# TRAY5.net
KiCad netlist of a schematic drawn in Altium Designer
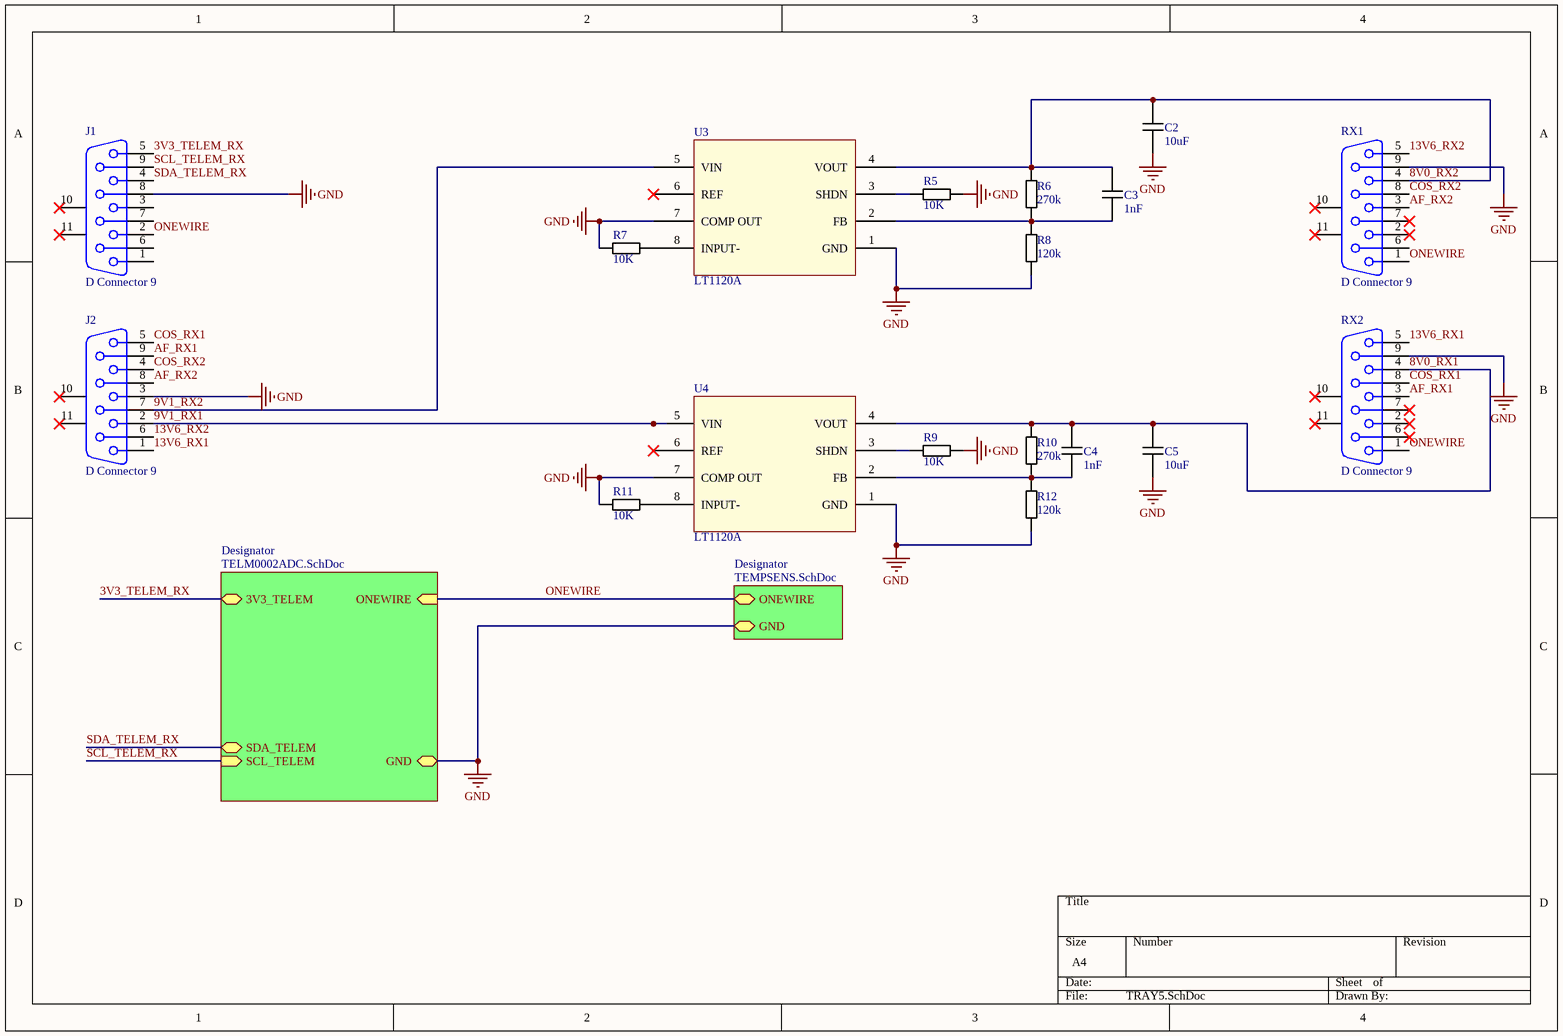
[diagram p0: TRAY5.SchDoc]

(export (version "E")
  (design (tool "Eeschema 10.0.6"))
  (components
    (comp (ref "C2")
      (value "10uF")
      (footprint "0805 Cap")
      (description "0805 MLCC - NP0, 5%")
      (fields (field (name "Comment") "0805 Cap"))
      (libsource (lib "Schlib1") (part "0805 MLCC - NP0, 5%"))
    )
    (comp (ref "C3")
      (value "1nF")
      (footprint "0805 Cap")
      (description "0805 MLCC - NP0, 5%")
      (fields (field (name "Comment") "0805 Cap"))
      (libsource (lib "Schlib1") (part "0805 MLCC - NP0, 5%"))
    )
    (comp (ref "C4")
      (value "1nF")
      (footprint "0805 Cap")
      (description "0805 MLCC - NP0, 5%")
      (fields (field (name "Comment") "0805 Cap"))
      (libsource (lib "Schlib1") (part "0805 MLCC - NP0, 5%"))
    )
    (comp (ref "C5")
      (value "10uF")
      (footprint "0805 Cap")
      (description "0805 MLCC - NP0, 5%")
      (fields (field (name "Comment") "0805 Cap"))
      (libsource (lib "Schlib1") (part "0805 MLCC - NP0, 5%"))
    )
    (comp (ref "J1")
      (value "D Connector 9")
      (footprint "DSUB1.385-2H9")
      (description "Receptacle Assembly, 9 Position, Right Angle")
      (libsource (lib "Miscellaneous Connectors") (part "D Connector 9"))
    )
    (comp (ref "J2")
      (value "D Connector 9")
      (footprint "DSUB1.385-2H9")
      (description "Receptacle Assembly, 9 Position, Right Angle")
      (libsource (lib "Miscellaneous Connectors") (part "D Connector 9"))
    )
    (comp (ref "R5")
      (value "10K")
      (footprint "0805 Resistor")
      (description "0805 Thick Film Resistor 1%")
      (fields (field (name "Comment") "0805 Resistor"))
      (libsource (lib "") (part "0805 Thick Film Resistor 1%_1"))
    )
    (comp (ref "R6")
      (value "270k")
      (footprint "0805 Resistor")
      (description "0805 Thick Film Resistor 1%")
      (fields (field (name "Comment") "0805 Resistor"))
      (libsource (lib "Schlib1") (part "0805 Thick Film Resistor 1%"))
    )
    (comp (ref "R7")
      (value "10K")
      (footprint "0805 Resistor")
      (description "0805 Thick Film Resistor 1%")
      (fields (field (name "Comment") "0805 Resistor"))
      (libsource (lib "") (part "0805 Thick Film Resistor 1%_1"))
    )
    (comp (ref "R8")
      (value "120k")
      (footprint "0805 Resistor")
      (description "0805 Thick Film Resistor 1%")
      (fields (field (name "Comment") "0805 Resistor"))
      (libsource (lib "Schlib1") (part "0805 Thick Film Resistor 1%"))
    )
    (comp (ref "R9")
      (value "10K")
      (footprint "0805 Resistor")
      (description "0805 Thick Film Resistor 1%")
      (fields (field (name "Comment") "0805 Resistor"))
      (libsource (lib "") (part "0805 Thick Film Resistor 1%_1"))
    )
    (comp (ref "R10")
      (value "270k")
      (footprint "0805 Resistor")
      (description "0805 Thick Film Resistor 1%")
      (fields (field (name "Comment") "0805 Resistor"))
      (libsource (lib "Schlib1") (part "0805 Thick Film Resistor 1%"))
    )
    (comp (ref "R11")
      (value "10K")
      (footprint "0805 Resistor")
      (description "0805 Thick Film Resistor 1%")
      (fields (field (name "Comment") "0805 Resistor"))
      (libsource (lib "") (part "0805 Thick Film Resistor 1%_1"))
    )
    (comp (ref "R12")
      (value "120k")
      (footprint "0805 Resistor")
      (description "0805 Thick Film Resistor 1%")
      (fields (field (name "Comment") "0805 Resistor"))
      (libsource (lib "Schlib1") (part "0805 Thick Film Resistor 1%"))
    )
    (comp (ref "RX1")
      (value "D Connector 9")
      (footprint "DSUB Upright")
      (description "Receptacle Assembly, 9 Position, Right Angle")
      (libsource (lib "Miscellaneous Connectors") (part "D Connector 9"))
    )
    (comp (ref "RX2")
      (value "D Connector 9")
      (footprint "DSUB Upright")
      (description "Receptacle Assembly, 9 Position, Right Angle")
      (libsource (lib "Miscellaneous Connectors") (part "D Connector 9"))
    )
    (comp (ref "U3")
      (value "LT1120A")
      (footprint "SOIC8 - LT1120A")
      (libsource (lib "Schlib1") (part "LT1120A"))
    )
    (comp (ref "U4")
      (value "LT1120A")
      (footprint "SOIC8 - LT1120A")
      (libsource (lib "Schlib1") (part "LT1120A"))
    )
  )
  (nets
    (net (code "1") (name "/3V3_TELEM_RX") (class "Default")
      (node (ref "J1") (pin "5") (pinfunction "5_5") (pintype "passive"))
    )
    (net (code "2") (name "/8V0_RX1") (class "Default")
      (node (ref "C4") (pin "2") (pinfunction "2_2") (pintype "passive"))
      (node (ref "C5") (pin "2") (pinfunction "2_2") (pintype "passive"))
      (node (ref "R10") (pin "2") (pinfunction "2_2") (pintype "passive"))
      (node (ref "RX2") (pin "4") (pinfunction "4_4") (pintype "passive"))
      (node (ref "U4") (pin "4") (pinfunction "VOUT_4") (pintype "passive"))
    )
    (net (code "3") (name "/8V0_RX2") (class "Default")
      (node (ref "C2") (pin "2") (pinfunction "2_2") (pintype "passive"))
      (node (ref "C3") (pin "2") (pinfunction "2_2") (pintype "passive"))
      (node (ref "R6") (pin "2") (pinfunction "2_2") (pintype "passive"))
      (node (ref "RX1") (pin "4") (pinfunction "4_4") (pintype "passive"))
      (node (ref "U3") (pin "4") (pinfunction "VOUT_4") (pintype "passive"))
    )
    (net (code "4") (name "/9V1_RX1") (class "Default")
      (node (ref "J2") (pin "2") (pinfunction "2_2") (pintype "passive"))
      (node (ref "U4") (pin "5") (pinfunction "VIN_5") (pintype "passive"))
    )
    (net (code "5") (name "/9V1_RX2") (class "Default")
      (node (ref "J2") (pin "7") (pinfunction "7_7") (pintype "passive"))
      (node (ref "U3") (pin "5") (pinfunction "VIN_5") (pintype "passive"))
    )
    (net (code "6") (name "/13V6_RX1") (class "Default")
      (node (ref "J2") (pin "1") (pinfunction "1_1") (pintype "passive"))
      (node (ref "RX2") (pin "5") (pinfunction "5_5") (pintype "passive"))
    )
    (net (code "7") (name "/13V6_RX2") (class "Default")
      (node (ref "J2") (pin "6") (pinfunction "6_6") (pintype "passive"))
      (node (ref "RX1") (pin "5") (pinfunction "5_5") (pintype "passive"))
    )
    (net (code "8") (name "/AF_RX1") (class "Default")
      (node (ref "J2") (pin "9") (pinfunction "9_9") (pintype "passive"))
      (node (ref "RX2") (pin "3") (pinfunction "3_3") (pintype "passive"))
    )
    (net (code "9") (name "/AF_RX2") (class "Default")
      (node (ref "J2") (pin "8") (pinfunction "8_8") (pintype "passive"))
      (node (ref "RX1") (pin "3") (pinfunction "3_3") (pintype "passive"))
    )
    (net (code "10") (name "/COS_RX1") (class "Default")
      (node (ref "J2") (pin "5") (pinfunction "5_5") (pintype "passive"))
      (node (ref "RX2") (pin "8") (pinfunction "8_8") (pintype "passive"))
    )
    (net (code "11") (name "/COS_RX2") (class "Default")
      (node (ref "J2") (pin "4") (pinfunction "4_4") (pintype "passive"))
      (node (ref "RX1") (pin "8") (pinfunction "8_8") (pintype "passive"))
    )
    (net (code "12") (name "/ONEWIRE") (class "Default")
      (node (ref "J1") (pin "2") (pinfunction "2_2") (pintype "passive"))
      (node (ref "RX1") (pin "1") (pinfunction "1_1") (pintype "passive"))
      (node (ref "RX2") (pin "1") (pinfunction "1_1") (pintype "passive"))
    )
    (net (code "13") (name "/SCL_TELEM_RX") (class "Default")
      (node (ref "J1") (pin "9") (pinfunction "9_9") (pintype "passive"))
    )
    (net (code "14") (name "/SDA_TELEM_RX") (class "Default")
      (node (ref "J1") (pin "4") (pinfunction "4_4") (pintype "passive"))
    )
    (net (code "15") (name "GND") (class "Default")
      (node (ref "C2") (pin "1") (pinfunction "1_1") (pintype "passive"))
      (node (ref "C5") (pin "1") (pinfunction "1_1") (pintype "passive"))
      (node (ref "J1") (pin "8") (pinfunction "8_8") (pintype "passive"))
      (node (ref "J2") (pin "3") (pinfunction "3_3") (pintype "passive"))
      (node (ref "R11") (pin "1") (pinfunction "1_1") (pintype "passive"))
      (node (ref "R12") (pin "1") (pinfunction "1_1") (pintype "passive"))
      (node (ref "R5") (pin "2") (pinfunction "2_2") (pintype "passive"))
      (node (ref "R7") (pin "1") (pinfunction "1_1") (pintype "passive"))
      (node (ref "R8") (pin "1") (pinfunction "1_1") (pintype "passive"))
      (node (ref "R9") (pin "2") (pinfunction "2_2") (pintype "passive"))
      (node (ref "RX1") (pin "9") (pinfunction "9_9") (pintype "passive"))
      (node (ref "RX2") (pin "9") (pinfunction "9_9") (pintype "passive"))
      (node (ref "U3") (pin "1") (pinfunction "GND_1") (pintype "passive"))
      (node (ref "U3") (pin "7") (pinfunction "COMP_OUT_7") (pintype "passive"))
      (node (ref "U4") (pin "1") (pinfunction "GND_1") (pintype "passive"))
      (node (ref "U4") (pin "7") (pinfunction "COMP_OUT_7") (pintype "passive"))
    )
    (net (code "16") (name "Net-(U3-FB)") (class "Default")
      (node (ref "C3") (pin "1") (pinfunction "1_1") (pintype "passive"))
      (node (ref "R6") (pin "1") (pinfunction "1_1") (pintype "passive"))
      (node (ref "R8") (pin "2") (pinfunction "2_2") (pintype "passive"))
      (node (ref "U3") (pin "2") (pinfunction "FB_2") (pintype "passive"))
    )
    (net (code "17") (name "Net-(U3-INPUT-)") (class "Default")
      (node (ref "R7") (pin "2") (pinfunction "2_2") (pintype "passive"))
      (node (ref "U3") (pin "8") (pinfunction "INPUT-_8") (pintype "passive"))
    )
    (net (code "18") (name "Net-(U3-SHDN)") (class "Default")
      (node (ref "R5") (pin "1") (pinfunction "1_1") (pintype "passive"))
      (node (ref "U3") (pin "3") (pinfunction "SHDN_3") (pintype "passive"))
    )
    (net (code "19") (name "Net-(U4-FB)") (class "Default")
      (node (ref "C4") (pin "1") (pinfunction "1_1") (pintype "passive"))
      (node (ref "R10") (pin "1") (pinfunction "1_1") (pintype "passive"))
      (node (ref "R12") (pin "2") (pinfunction "2_2") (pintype "passive"))
      (node (ref "U4") (pin "2") (pinfunction "FB_2") (pintype "passive"))
    )
    (net (code "20") (name "Net-(U4-INPUT-)") (class "Default")
      (node (ref "R11") (pin "2") (pinfunction "2_2") (pintype "passive"))
      (node (ref "U4") (pin "8") (pinfunction "INPUT-_8") (pintype "passive"))
    )
    (net (code "21") (name "Net-(U4-SHDN)") (class "Default")
      (node (ref "R9") (pin "1") (pinfunction "1_1") (pintype "passive"))
      (node (ref "U4") (pin "3") (pinfunction "SHDN_3") (pintype "passive"))
    )
    (net (code "22") (name "unconnected-(J1-MH1-Pad10)") (class "Default")
      (node (ref "J1") (pin "10") (pinfunction "MH1_10") (pintype "passive+no_connect"))
    )
    (net (code "23") (name "unconnected-(J1-MH2-Pad11)") (class "Default")
      (node (ref "J1") (pin "11") (pinfunction "MH2_11") (pintype "passive+no_connect"))
    )
    (net (code "24") (name "unconnected-(J1-Pad1)") (class "Default")
      (node (ref "J1") (pin "1") (pinfunction "1_1") (pintype "passive"))
    )
    (net (code "25") (name "unconnected-(J1-Pad3)") (class "Default")
      (node (ref "J1") (pin "3") (pinfunction "3_3") (pintype "passive"))
    )
    (net (code "26") (name "unconnected-(J1-Pad6)") (class "Default")
      (node (ref "J1") (pin "6") (pinfunction "6_6") (pintype "passive"))
    )
    (net (code "27") (name "unconnected-(J1-Pad7)") (class "Default")
      (node (ref "J1") (pin "7") (pinfunction "7_7") (pintype "passive"))
    )
    (net (code "28") (name "unconnected-(J2-MH1-Pad10)") (class "Default")
      (node (ref "J2") (pin "10") (pinfunction "MH1_10") (pintype "passive+no_connect"))
    )
    (net (code "29") (name "unconnected-(J2-MH2-Pad11)") (class "Default")
      (node (ref "J2") (pin "11") (pinfunction "MH2_11") (pintype "passive+no_connect"))
    )
    (net (code "30") (name "unconnected-(RX1-MH1-Pad10)") (class "Default")
      (node (ref "RX1") (pin "10") (pinfunction "MH1_10") (pintype "passive+no_connect"))
    )
    (net (code "31") (name "unconnected-(RX1-MH2-Pad11)") (class "Default")
      (node (ref "RX1") (pin "11") (pinfunction "MH2_11") (pintype "passive+no_connect"))
    )
    (net (code "32") (name "unconnected-(RX1-Pad2)") (class "Default")
      (node (ref "RX1") (pin "2") (pinfunction "2_2") (pintype "passive+no_connect"))
    )
    (net (code "33") (name "unconnected-(RX1-Pad6)") (class "Default")
      (node (ref "RX1") (pin "6") (pinfunction "6_6") (pintype "passive"))
    )
    (net (code "34") (name "unconnected-(RX1-Pad7)") (class "Default")
      (node (ref "RX1") (pin "7") (pinfunction "7_7") (pintype "passive+no_connect"))
    )
    (net (code "35") (name "unconnected-(RX2-MH1-Pad10)") (class "Default")
      (node (ref "RX2") (pin "10") (pinfunction "MH1_10") (pintype "passive+no_connect"))
    )
    (net (code "36") (name "unconnected-(RX2-MH2-Pad11)") (class "Default")
      (node (ref "RX2") (pin "11") (pinfunction "MH2_11") (pintype "passive+no_connect"))
    )
    (net (code "37") (name "unconnected-(RX2-Pad2)") (class "Default")
      (node (ref "RX2") (pin "2") (pinfunction "2_2") (pintype "passive+no_connect"))
    )
    (net (code "38") (name "unconnected-(RX2-Pad6)") (class "Default")
      (node (ref "RX2") (pin "6") (pinfunction "6_6") (pintype "passive+no_connect"))
    )
    (net (code "39") (name "unconnected-(RX2-Pad7)") (class "Default")
      (node (ref "RX2") (pin "7") (pinfunction "7_7") (pintype "passive+no_connect"))
    )
    (net (code "40") (name "unconnected-(U3-REF-Pad6)") (class "Default")
      (node (ref "U3") (pin "6") (pinfunction "REF_6") (pintype "passive+no_connect"))
    )
    (net (code "41") (name "unconnected-(U4-REF-Pad6)") (class "Default")
      (node (ref "U4") (pin "6") (pinfunction "REF_6") (pintype "passive+no_connect"))
    )
  )
)
